# BM_EXT_PWR.net
KiCad netlist of a schematic drawn in Altium Designer
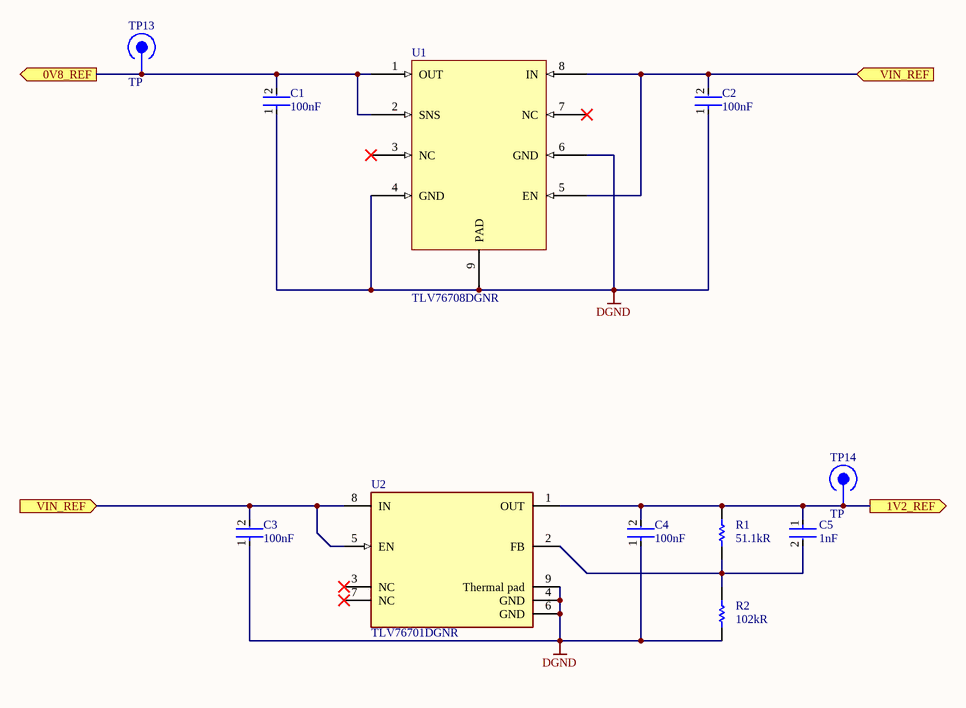
[diagram p0: BM_EXT_PWR.SchDoc]

(export (version "E")
  (design (tool "Eeschema 10.0.6"))
  (components
    (comp (ref "C1")
      (value "100nF")
      (footprint "FP-CC0402-IPC_B")
      (fields (field (name "Comment") "CC0402KRX7R9BB104"))
      (libsource (lib "Digital Shovel") (part "11868f565c42a9108669ba33697ecf6"))
    )
    (comp (ref "C2")
      (value "100nF")
      (footprint "FP-CC0402-IPC_B")
      (fields (field (name "Comment") "CC0402KRX7R9BB104"))
      (libsource (lib "Digital Shovel") (part "11868f565c42a9108669ba33697ecf6"))
    )
    (comp (ref "C3")
      (value "100nF")
      (footprint "FP-CC0402-IPC_B")
      (fields (field (name "Comment") "CC0402KRX7R9BB104"))
      (libsource (lib "Digital Shovel") (part "11868f565c42a9108669ba33697ecf6"))
    )
    (comp (ref "C4")
      (value "100nF")
      (footprint "FP-CC0402-IPC_B")
      (fields (field (name "Comment") "CC0402KRX7R9BB104"))
      (libsource (lib "Digital Shovel") (part "11868f565c42a9108669ba33697ecf6"))
    )
    (comp (ref "C5")
      (value "1nF")
      (footprint "FP-CC0805-0_85-MFG")
      (fields (field (name "Comment") "CC0805KRX7R9BB102"))
      (libsource (lib "Digital Shovel") (part "11868f565c42a9108669ba33697ecf6"))
    )
    (comp (ref "R1")
      (value "51.1kR")
      (footprint "RESC1005X40X25LL10T10")
      (fields (field (name "Comment") "RK73H1ETTP5112F"))
      (libsource (lib "Digital Shovel") (part "RES"))
    )
    (comp (ref "R2")
      (value "102kR")
      (footprint "RESC1005X40X25LL10T10")
      (fields (field (name "Comment") "RK73H1ETTP1023F"))
      (libsource (lib "Digital Shovel") (part "RES"))
    )
    (comp (ref "TP13")
      (value "TP")
      (footprint "TP-Footprint-1")
      (description "digital shovel test point")
      (libsource (lib "Digital Shovel") (part "TP-Symbol-1"))
    )
    (comp (ref "TP14")
      (value "TP")
      (footprint "TP-Footprint-1")
      (description "digital shovel test point")
      (libsource (lib "Digital Shovel") (part "TP-Symbol-1"))
    )
    (comp (ref "U1")
      (value "TLV76708DGNR")
      (footprint "TLV76708DGNR-Footprint-1")
      (libsource (lib "Digital Shovel") (part "TLV76708DGNR-Symbol-1"))
    )
    (comp (ref "U2")
      (value "TLV76701DGNR")
      (footprint "FP-DGN0008G-MFG")
      (description "Adjustable Positive Standard Regulator, 0.8V Min, 13.6V Max, PDSO8")
      (libsource (lib "Digital Shovel") (part "4137fefd6f2351a27154aa09bf60b26"))
    )
  )
  (nets
    (net (code "1") (name "/0V8_REF") (class "Default")
      (node (ref "C1") (pin "2") (pinfunction "2_2") (pintype "passive"))
      (node (ref "TP13") (pin "1") (pintype "passive"))
      (node (ref "U1") (pin "1") (pinfunction "OUT_1") (pintype "input"))
      (node (ref "U1") (pin "2") (pinfunction "SNS_2") (pintype "input"))
    )
    (net (code "2") (name "/1V2_REF") (class "Default")
      (node (ref "C4") (pin "2") (pinfunction "2_2") (pintype "passive"))
      (node (ref "C5") (pin "1") (pinfunction "1_1") (pintype "passive"))
      (node (ref "R1") (pin "2") (pinfunction "2_2") (pintype "passive"))
      (node (ref "TP14") (pin "1") (pintype "passive"))
      (node (ref "U2") (pin "1") (pinfunction "OUT_1") (pintype "passive"))
    )
    (net (code "3") (name "/VIN_REF") (class "Default")
      (node (ref "C2") (pin "2") (pinfunction "2_2") (pintype "passive"))
      (node (ref "C3") (pin "2") (pinfunction "2_2") (pintype "passive"))
      (node (ref "U1") (pin "5") (pinfunction "EN_5") (pintype "input"))
      (node (ref "U1") (pin "8") (pinfunction "IN_8") (pintype "input"))
      (node (ref "U2") (pin "5") (pinfunction "EN_5") (pintype "input"))
      (node (ref "U2") (pin "8") (pinfunction "IN_8") (pintype "power_in"))
    )
    (net (code "4") (name "DGND") (class "Default")
      (node (ref "C1") (pin "1") (pinfunction "1_1") (pintype "passive"))
      (node (ref "C2") (pin "1") (pinfunction "1_1") (pintype "passive"))
      (node (ref "C3") (pin "1") (pinfunction "1_1") (pintype "passive"))
      (node (ref "C4") (pin "1") (pinfunction "1_1") (pintype "passive"))
      (node (ref "R2") (pin "1") (pinfunction "1_1") (pintype "passive"))
      (node (ref "U1") (pin "4") (pinfunction "GND_4") (pintype "input"))
      (node (ref "U1") (pin "6") (pinfunction "GND_6") (pintype "input"))
      (node (ref "U1") (pin "9") (pinfunction "PAD_9") (pintype "passive"))
      (node (ref "U2") (pin "4") (pinfunction "GND_4") (pintype "power_in"))
      (node (ref "U2") (pin "6") (pinfunction "GND_6") (pintype "power_in"))
      (node (ref "U2") (pin "9") (pinfunction "Thermal_pad_9") (pintype "power_in"))
    )
    (net (code "5") (name "Net-(U2-FB)") (class "Default")
      (node (ref "C5") (pin "2") (pinfunction "2_2") (pintype "passive"))
      (node (ref "R1") (pin "1") (pinfunction "1_1") (pintype "passive"))
      (node (ref "R2") (pin "2") (pinfunction "2_2") (pintype "passive"))
      (node (ref "U2") (pin "2") (pinfunction "FB_2") (pintype "passive"))
    )
    (net (code "6") (name "unconnected-(U1-NC-Pad3)") (class "Default")
      (node (ref "U1") (pin "3") (pinfunction "NC_3") (pintype "input+no_connect"))
    )
    (net (code "7") (name "unconnected-(U1-NC-Pad7)") (class "Default")
      (node (ref "U1") (pin "7") (pinfunction "NC_7") (pintype "input+no_connect"))
    )
    (net (code "8") (name "unconnected-(U2-NC-Pad3)") (class "Default")
      (node (ref "U2") (pin "3") (pinfunction "NC_3") (pintype "passive+no_connect"))
    )
    (net (code "9") (name "unconnected-(U2-NC-Pad7)") (class "Default")
      (node (ref "U2") (pin "7") (pinfunction "NC_7") (pintype "passive+no_connect"))
    )
  )
)
